# SCH_JCTestBoard_2025-03-01.net
KiCad netlist of a schematic drawn in EasyEDA
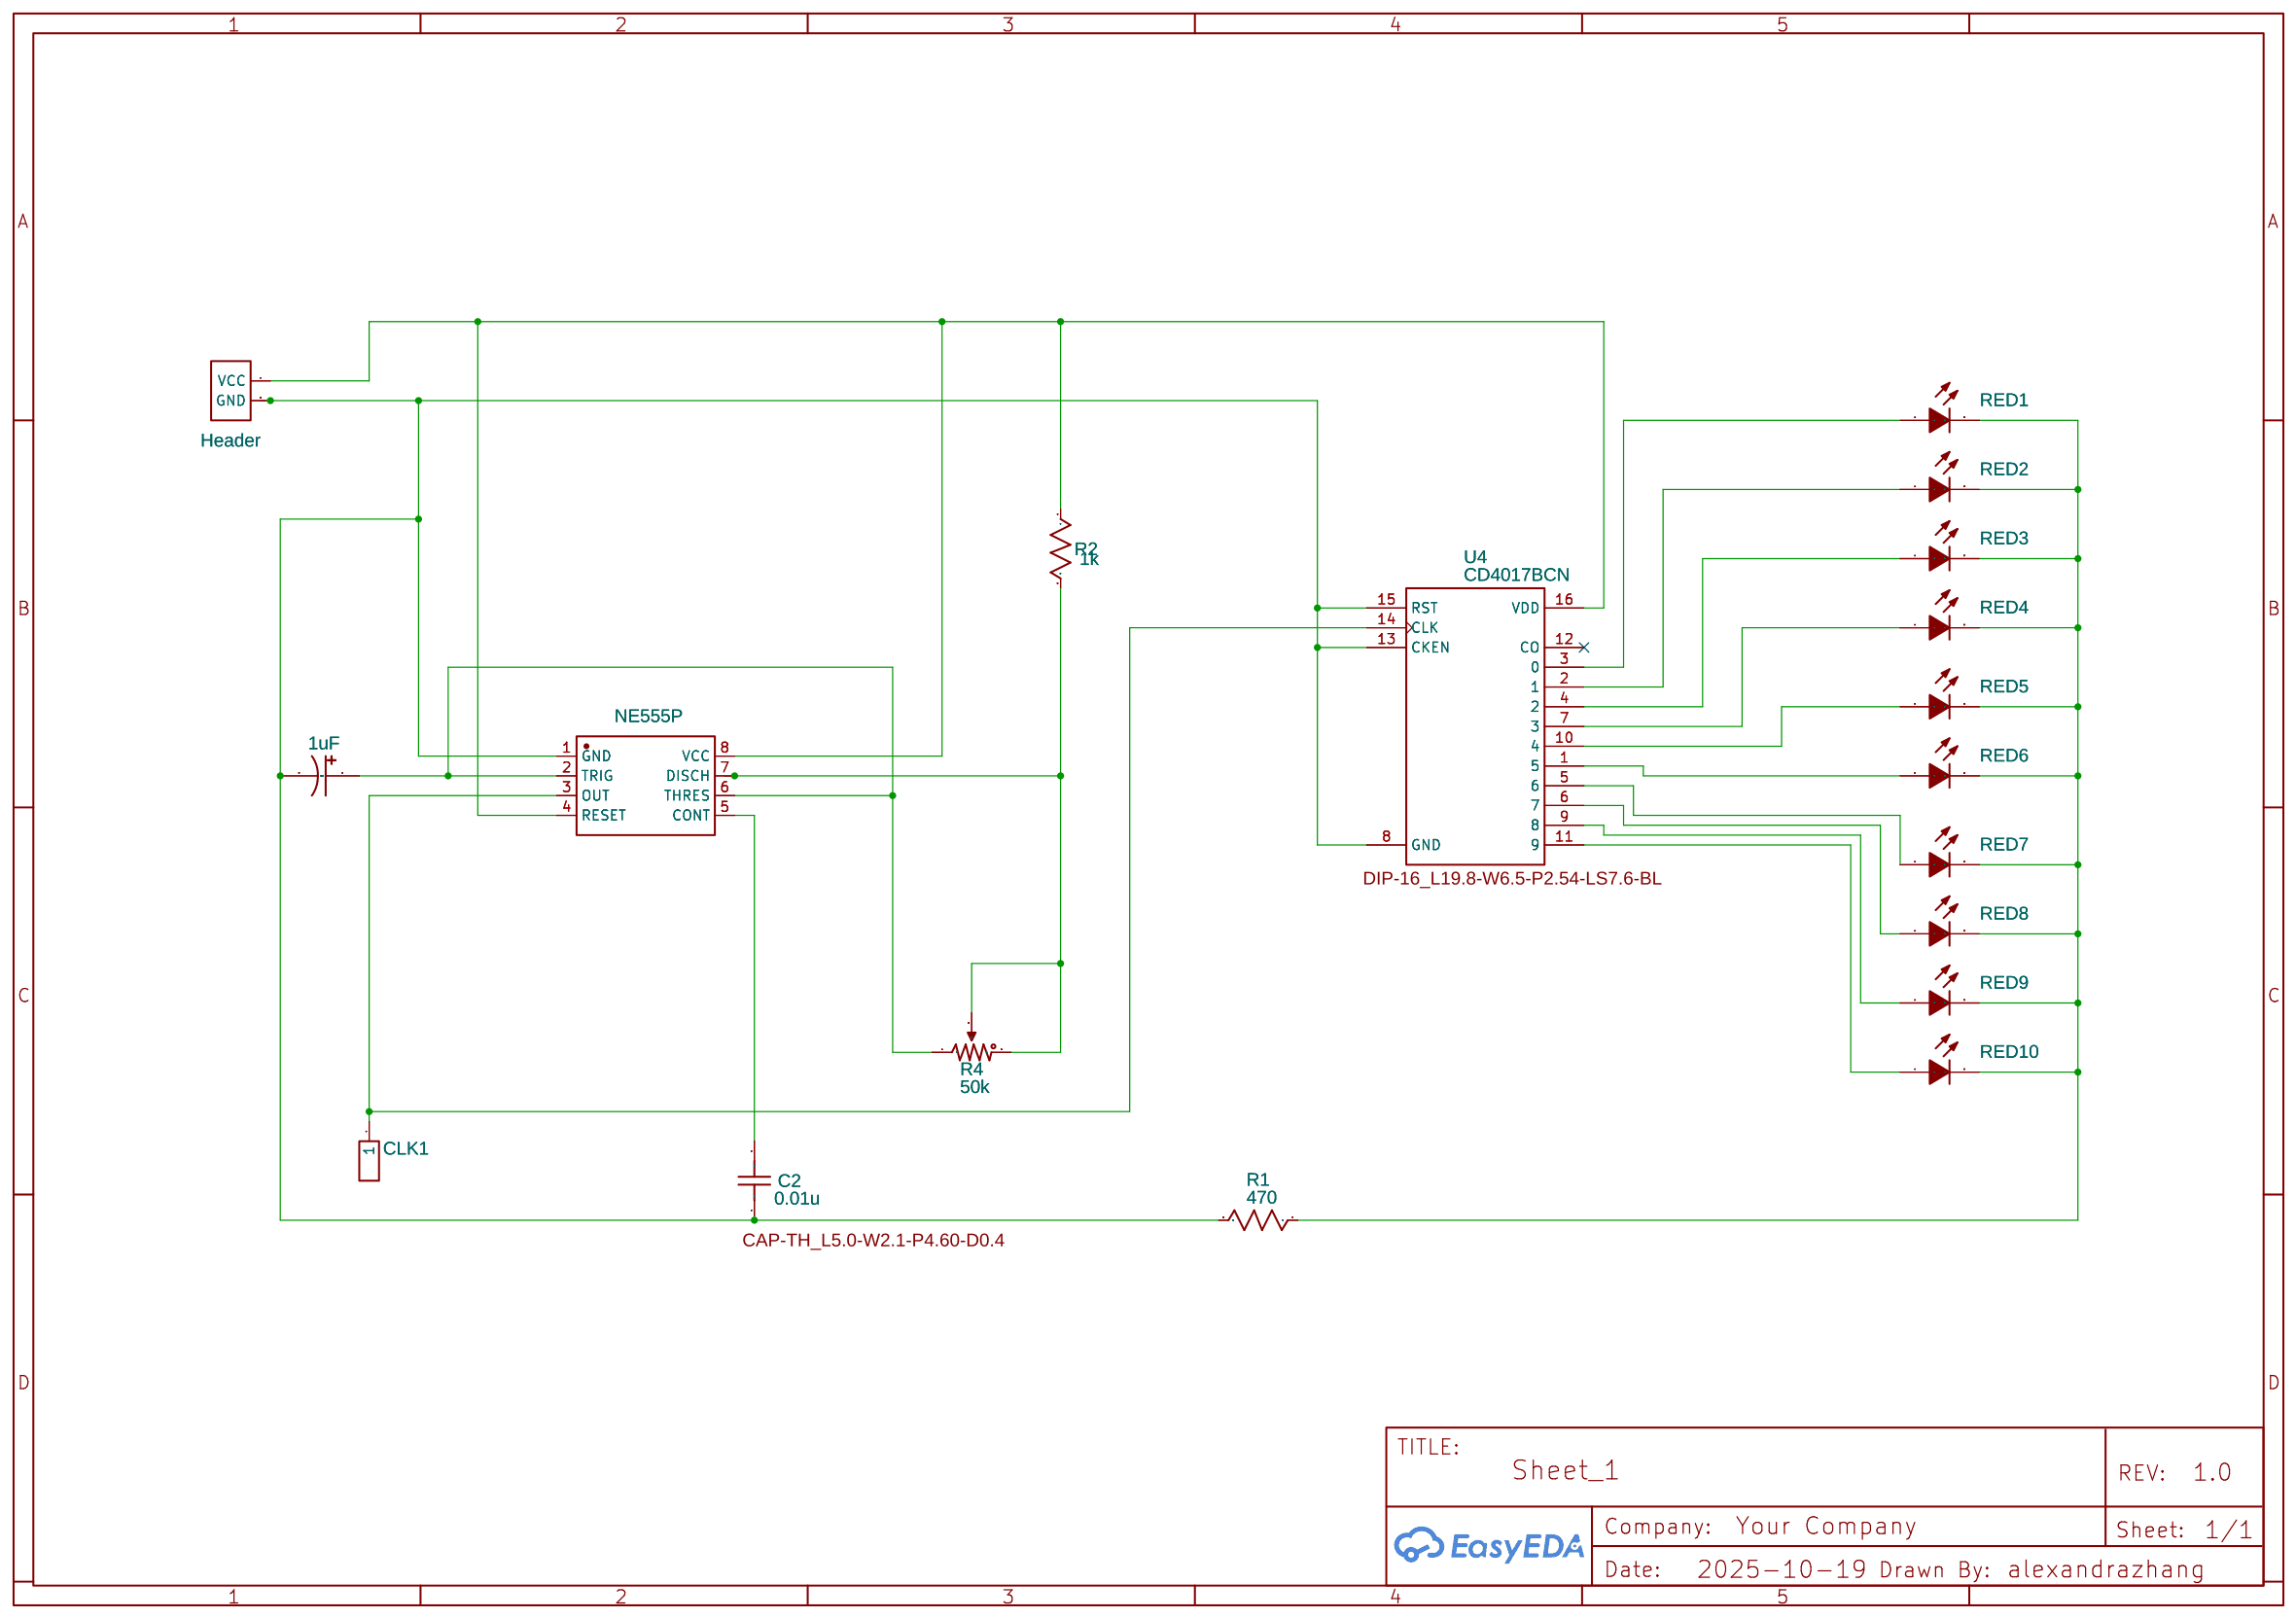
[diagram p0: schematic sheet]

(export (version "E")
  (design (tool "Eeschema 10.0.6"))
  (components
    (comp (ref "C1")
      (value "1uF")
      (fields (field (name "Manufacturer Part") "UVZ1H010MDD") (field (name "Manufacturer") "Nichicon(尼吉康)"))
      (libsource (lib "") (part "UVZ1H010MDD"))
    )
    (comp (ref "C2") (value "0.01u") (libsource (lib "") (part "C_0603_US")))
    (comp (ref "CLK1")
      (value "C81276")
      (fields
        (field (name "Manufacturer Part") "2.54-1*1P针")
        (field (name "Manufacturer") "BOOMELE(Boom Precision Elec)")
      )
      (libsource (lib "") (part "Header-Male-2.54_1x1"))
    )
    (comp (ref "H1") (value "Header") (libsource (lib "") (part "HEADER-FEMALE-2.54_1X2")))
    (comp (ref "R1")
      (value "470")
      (fields (field (name "Manufacturer Part") "?"))
      (libsource (lib "") (part "Resistor_1"))
    )
    (comp (ref "R2")
      (value "1k")
      (fields (field (name "Manufacturer Part") "?"))
      (libsource (lib "") (part "Resistor"))
    )
    (comp (ref "R4")
      (value "50k")
      (fields (field (name "Manufacturer Part") "?"))
      (libsource (lib "") (part "Potentiometer"))
    )
    (comp (ref "RED1") (value "LED_5MM") (libsource (lib "") (part "LED_5MM")))
    (comp (ref "RED2") (value "LED_5MM") (libsource (lib "") (part "LED_5MM")))
    (comp (ref "RED3") (value "LED_5MM") (libsource (lib "") (part "LED_5MM")))
    (comp (ref "RED4") (value "LED_5MM") (libsource (lib "") (part "LED_5MM")))
    (comp (ref "RED5") (value "LED_5MM") (libsource (lib "") (part "LED_5MM")))
    (comp (ref "RED6") (value "LED_5MM") (libsource (lib "") (part "LED_5MM")))
    (comp (ref "RED7") (value "LED_5MM") (libsource (lib "") (part "LED_5MM")))
    (comp (ref "RED8") (value "LED_5MM") (libsource (lib "") (part "LED_5MM")))
    (comp (ref "RED9") (value "LED_5MM") (libsource (lib "") (part "LED_5MM")))
    (comp (ref "RED10") (value "LED_5MM") (libsource (lib "") (part "LED_5MM")))
    (comp (ref "U2")
      (value "NE555P")
      (fields (field (name "Manufacturer") "TI(德州仪器)"))
      (libsource (lib "") (part "NE555P"))
    )
    (comp (ref "U4") (value "CD4017BCN") (libsource (lib "") (part "CD4017BCN")))
  )
  (nets
    (net (code "1") (name "Net-(H1-GND)") (class "Default")
      (node (ref "C1") (pin "2") (pinfunction "2_2") (pintype "unspecified"))
      (node (ref "C2") (pin "1") (pinfunction "1_1") (pintype "unspecified"))
      (node (ref "H1") (pin "2") (pinfunction "GND_2") (pintype "unspecified"))
      (node (ref "R1") (pin "2") (pinfunction "2_2") (pintype "unspecified"))
      (node (ref "U2") (pin "1") (pinfunction "GND_1") (pintype "unspecified"))
      (node (ref "U4") (pin "13") (pinfunction "CKEN_13") (pintype "unspecified"))
      (node (ref "U4") (pin "15") (pinfunction "RST_15") (pintype "unspecified"))
      (node (ref "U4") (pin "8") (pinfunction "GND_8") (pintype "passive"))
    )
    (net (code "2") (name "Net-(H1-VCC)") (class "Default")
      (node (ref "H1") (pin "1") (pinfunction "VCC_1") (pintype "unspecified"))
      (node (ref "R2") (pin "1") (pinfunction "1_1") (pintype "unspecified"))
      (node (ref "U2") (pin "4") (pinfunction "RESET_4") (pintype "unspecified"))
      (node (ref "U2") (pin "8") (pinfunction "VCC_8") (pintype "unspecified"))
      (node (ref "U4") (pin "16") (pinfunction "VDD_16") (pintype "passive"))
    )
    (net (code "3") (name "Net-(R4-2)") (class "Default")
      (node (ref "R2") (pin "2") (pinfunction "2_2") (pintype "unspecified"))
      (node (ref "R4") (pin "2") (pinfunction "3_2") (pintype "unspecified"))
      (node (ref "R4") (pin "3") (pinfunction "2_3") (pintype "unspecified"))
      (node (ref "U2") (pin "7") (pinfunction "DISCH_7") (pintype "unspecified"))
    )
    (net (code "4") (name "Net-(RED1-A)") (class "Default")
      (node (ref "RED1") (pin "1") (pinfunction "A_1") (pintype "input"))
      (node (ref "U4") (pin "3") (pinfunction "0_3") (pintype "output"))
    )
    (net (code "5") (name "Net-(RED1-K)") (class "Default")
      (node (ref "R1") (pin "1") (pinfunction "1_1") (pintype "unspecified"))
      (node (ref "RED1") (pin "2") (pinfunction "K_2") (pintype "input"))
      (node (ref "RED10") (pin "2") (pinfunction "K_2") (pintype "input"))
      (node (ref "RED2") (pin "2") (pinfunction "K_2") (pintype "input"))
      (node (ref "RED3") (pin "2") (pinfunction "K_2") (pintype "input"))
      (node (ref "RED4") (pin "2") (pinfunction "K_2") (pintype "input"))
      (node (ref "RED5") (pin "2") (pinfunction "K_2") (pintype "input"))
      (node (ref "RED6") (pin "2") (pinfunction "K_2") (pintype "input"))
      (node (ref "RED7") (pin "2") (pinfunction "K_2") (pintype "input"))
      (node (ref "RED8") (pin "2") (pinfunction "K_2") (pintype "input"))
      (node (ref "RED9") (pin "2") (pinfunction "K_2") (pintype "input"))
    )
    (net (code "6") (name "Net-(RED2-A)") (class "Default")
      (node (ref "RED2") (pin "1") (pinfunction "A_1") (pintype "input"))
      (node (ref "U4") (pin "2") (pinfunction "1_2") (pintype "output"))
    )
    (net (code "7") (name "Net-(RED3-A)") (class "Default")
      (node (ref "RED3") (pin "1") (pinfunction "A_1") (pintype "input"))
      (node (ref "U4") (pin "4") (pinfunction "2_4") (pintype "output"))
    )
    (net (code "8") (name "Net-(RED4-A)") (class "Default")
      (node (ref "RED4") (pin "1") (pinfunction "A_1") (pintype "input"))
      (node (ref "U4") (pin "7") (pinfunction "3_7") (pintype "output"))
    )
    (net (code "9") (name "Net-(RED5-A)") (class "Default")
      (node (ref "RED5") (pin "1") (pinfunction "A_1") (pintype "input"))
      (node (ref "U4") (pin "10") (pinfunction "4_10") (pintype "output"))
    )
    (net (code "10") (name "Net-(RED6-A)") (class "Default")
      (node (ref "RED6") (pin "1") (pinfunction "A_1") (pintype "input"))
      (node (ref "U4") (pin "1") (pinfunction "5_1") (pintype "output"))
    )
    (net (code "11") (name "Net-(RED7-A)") (class "Default")
      (node (ref "RED7") (pin "1") (pinfunction "A_1") (pintype "input"))
      (node (ref "U4") (pin "5") (pinfunction "6_5") (pintype "output"))
    )
    (net (code "12") (name "Net-(RED8-A)") (class "Default")
      (node (ref "RED8") (pin "1") (pinfunction "A_1") (pintype "input"))
      (node (ref "U4") (pin "6") (pinfunction "7_6") (pintype "output"))
    )
    (net (code "13") (name "Net-(RED9-A)") (class "Default")
      (node (ref "RED9") (pin "1") (pinfunction "A_1") (pintype "input"))
      (node (ref "U4") (pin "9") (pinfunction "8_9") (pintype "output"))
    )
    (net (code "14") (name "Net-(RED10-A)") (class "Default")
      (node (ref "RED10") (pin "1") (pinfunction "A_1") (pintype "input"))
      (node (ref "U4") (pin "11") (pinfunction "9_11") (pintype "output"))
    )
    (net (code "15") (name "Net-(U2-CONT)") (class "Default")
      (node (ref "C2") (pin "2") (pinfunction "2_2") (pintype "unspecified"))
      (node (ref "U2") (pin "5") (pinfunction "CONT_5") (pintype "unspecified"))
    )
    (net (code "16") (name "Net-(U2-OUT)") (class "Default")
      (node (ref "CLK1") (pin "1") (pinfunction "1_1") (pintype "unspecified"))
      (node (ref "U2") (pin "3") (pinfunction "OUT_3") (pintype "unspecified"))
      (node (ref "U4") (pin "14") (pinfunction "CLK_14") (pintype "unspecified"))
    )
    (net (code "17") (name "Net-(U2-THRES)") (class "Default")
      (node (ref "C1") (pin "1") (pinfunction "1_1") (pintype "unspecified"))
      (node (ref "R4") (pin "1") (pinfunction "1_1") (pintype "unspecified"))
      (node (ref "U2") (pin "2") (pinfunction "TRIG_2") (pintype "unspecified"))
      (node (ref "U2") (pin "6") (pinfunction "THRES_6") (pintype "unspecified"))
    )
    (net (code "18") (name "unconnected-(U4-CO-Pad12)") (class "Default")
      (node (ref "U4") (pin "12") (pinfunction "CO_12") (pintype "output+no_connect"))
    )
  )
)
